# CSMS.net
KiCad netlist of a schematic drawn in Altium Designer
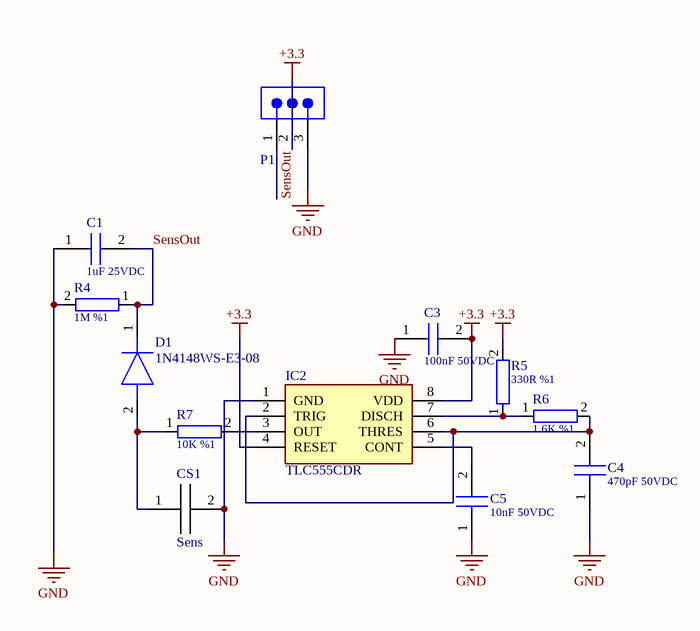
[diagram p0: CSMS.SchDoc]

(export (version "E")
  (design (tool "Eeschema 10.0.6"))
  (components
    (comp (ref "C1")
      (value "1uF 25VDC")
      (footprint "0603 CAP")
      (description "1uF 25VDC ±10% X7R MLCC 0603")
      (fields (field (name "Comment") "CL10B105KA8NNNC"))
      (libsource (lib "CSMS") (part "CL10B105KA8NNNC"))
    )
    (comp (ref "C3")
      (value "100nF 50VDC")
      (footprint "0603 CAP")
      (description "100nF 50VDC ±10% X7R MLCC 0603")
      (fields (field (name "Comment") "CL10B104KB8NNNC"))
      (libsource (lib "CSMS") (part "CL10B104KB8NNNC"))
    )
    (comp (ref "C4")
      (value "470pF 50VDC")
      (footprint "0603 CAP")
      (description "470pF 50VDC ±10% X7R MLCC 0603")
      (fields (field (name "Comment") "CL10B471KB8NNNC"))
      (libsource (lib "CSMS") (part "CL10B471KB8NNNC"))
    )
    (comp (ref "C5")
      (value "10nF 50VDC")
      (footprint "0603 CAP")
      (description "10nF, 50 V, ± 10%, X7R, 0603, Multilayer Ceramic Capacitor,")
      (fields (field (name "Comment") "CC0603KRX7R9BB103"))
      (libsource (lib "CSMS") (part "CC0603KRX7R9BB103"))
    )
    (comp (ref "CS1")
      (value "Sens")
      (footprint "Sens")
      (description "Pcb Sens")
      (libsource (lib "CSMS") (part "Sens"))
    )
    (comp (ref "D1")
      (value "1N4148WS-E3-08")
      (footprint "SOD2513X110N")
      (description "Diode")
      (fields (field (name "MOUSER PART NUMBER") "78-1N4148WS-E3-08"))
      (libsource (lib "CSMS") (part "1N4148WS-E3-08"))
    )
    (comp (ref "IC2")
      (value "TLC555CDR")
      (footprint "SOIC127P600X175-8N")
      (description "555 Astable 2.1-MHz, 250-µA, Low-Power Timer 8-SOIC 0 to 70")
      (fields (field (name "MOUSER PART NUMBER") "595-TLC555CDR"))
      (libsource (lib "CSMS") (part "TLC555CDR"))
    )
    (comp (ref "P1")
      (value "61300311021")
      (footprint "61300311021")
      (description "WR-PHD Pin Header, THT, Angled, pitch 2.54mm, 1 Row, 3P")
      (fields (field (name "MANUFACTURER") "Wurth Elektronik"))
      (libsource (lib "CSMS") (part "61300311021"))
    )
    (comp (ref "R4")
      (value "1M %1")
      (footprint "0603 RES")
      (description "1M Ohms 1% 1/10W-S 100PPM RES 0603")
      (fields (field (name "Comment") "0603SAF1004T5E"))
      (libsource (lib "CSMS") (part "0603SAF1004T5E"))
    )
    (comp (ref "R5")
      (value "330R %1")
      (footprint "0603 RES")
      (description "330R Ohms 1% 1/10W-S 100PPM RES 0603")
      (fields (field (name "Comment") "0603SAF3300T5E"))
      (libsource (lib "CSMS") (part "0603SAF3300T5E"))
    )
    (comp (ref "R6")
      (value "1.6K %1")
      (footprint "0603 RES")
      (description "1.6K Ohms 1% 1/10W-S 100PPM RES 0603")
      (fields (field (name "Comment") "0603SAF1601T5E"))
      (libsource (lib "CSMS") (part "0603SAF1601T5E"))
    )
    (comp (ref "R7")
      (value "10K %1")
      (footprint "0603 RES")
      (description "10K Ohms 1% 1/10W-S 100PPM RES 0603")
      (fields (field (name "Comment") "0603SAF1002T5E"))
      (libsource (lib "CSMS") (part "0603SAF1002T5E"))
    )
  )
  (nets
    (net (code "1") (name "+3.3") (class "Default")
      (node (ref "C3") (pin "2") (pinfunction "2_2") (pintype "passive"))
      (node (ref "IC2") (pin "4") (pinfunction "RESET_4") (pintype "passive"))
      (node (ref "IC2") (pin "8") (pinfunction "VDD_8") (pintype "passive"))
      (node (ref "P1") (pin "2") (pinfunction "2_2") (pintype "passive"))
      (node (ref "R5") (pin "2") (pinfunction "2_2") (pintype "passive"))
    )
    (net (code "2") (name "/SensOut") (class "Default")
      (node (ref "C1") (pin "2") (pinfunction "2_2") (pintype "passive"))
      (node (ref "D1") (pin "1") (pinfunction "K_1") (pintype "passive"))
      (node (ref "P1") (pin "1") (pinfunction "1_1") (pintype "passive"))
      (node (ref "R4") (pin "1") (pinfunction "1_1") (pintype "passive"))
    )
    (net (code "3") (name "GND") (class "Default")
      (node (ref "C1") (pin "1") (pinfunction "1_1") (pintype "passive"))
      (node (ref "C3") (pin "1") (pinfunction "1_1") (pintype "passive"))
      (node (ref "C4") (pin "1") (pinfunction "1_1") (pintype "passive"))
      (node (ref "C5") (pin "1") (pinfunction "1_1") (pintype "passive"))
      (node (ref "CS1") (pin "2") (pinfunction "2_2") (pintype "passive"))
      (node (ref "IC2") (pin "1") (pinfunction "GND_1") (pintype "passive"))
      (node (ref "P1") (pin "3") (pinfunction "3_3") (pintype "passive"))
      (node (ref "R4") (pin "2") (pinfunction "2_2") (pintype "passive"))
    )
    (net (code "4") (name "Net-(D1-A)") (class "Default")
      (node (ref "CS1") (pin "1") (pinfunction "1_1") (pintype "passive"))
      (node (ref "D1") (pin "2") (pinfunction "A_2") (pintype "passive"))
      (node (ref "R7") (pin "1") (pinfunction "1_1") (pintype "passive"))
    )
    (net (code "5") (name "Net-(IC2-CONT)") (class "Default")
      (node (ref "C5") (pin "2") (pinfunction "2_2") (pintype "passive"))
      (node (ref "IC2") (pin "5") (pinfunction "CONT_5") (pintype "passive"))
    )
    (net (code "6") (name "Net-(IC2-DISCH)") (class "Default")
      (node (ref "IC2") (pin "7") (pinfunction "DISCH_7") (pintype "passive"))
      (node (ref "R5") (pin "1") (pinfunction "1_1") (pintype "passive"))
      (node (ref "R6") (pin "1") (pinfunction "1_1") (pintype "passive"))
    )
    (net (code "7") (name "Net-(IC2-OUT)") (class "Default")
      (node (ref "IC2") (pin "3") (pinfunction "OUT_3") (pintype "passive"))
      (node (ref "R7") (pin "2") (pinfunction "2_2") (pintype "passive"))
    )
    (net (code "8") (name "Net-(IC2-THRES)") (class "Default")
      (node (ref "C4") (pin "2") (pinfunction "2_2") (pintype "passive"))
      (node (ref "IC2") (pin "2") (pinfunction "TRIG_2") (pintype "passive"))
      (node (ref "IC2") (pin "6") (pinfunction "THRES_6") (pintype "passive"))
      (node (ref "R6") (pin "2") (pinfunction "2_2") (pintype "passive"))
    )
  )
)
